# Rectifiers.net
KiCad netlist of a schematic drawn in Altium Designer
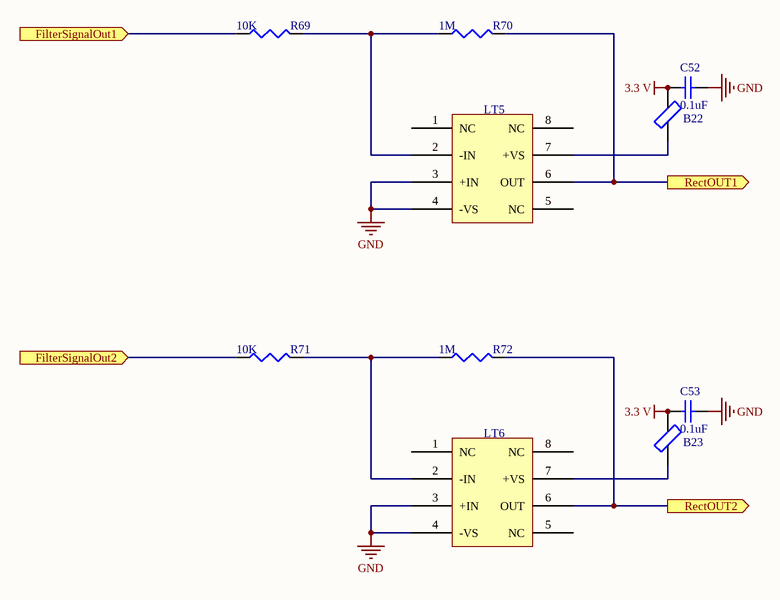
[diagram p0: Rectifiers.SchDoc]

(export (version "E")
  (design (tool "Eeschema 10.0.6"))
  (components
    (comp (ref "B22")
      (value "Ferrite Bead")
      (footprint "Resistor 0603")
      (libsource (lib "PMUD") (part "Ferrite Bead"))
    )
    (comp (ref "B23")
      (value "Ferrite Bead")
      (footprint "Resistor 0603")
      (libsource (lib "PMUD") (part "Ferrite Bead"))
    )
    (comp (ref "C52")
      (value "0.1uF")
      (footprint "C1206")
      (description "Capacitor (Semiconductor SIM Model)")
      (fields (field (name "Comment") ".1uF 20V Ceramic Low ESR") (field (name "PUBLISHER") "Altium Limited"))
      (libsource (lib "Miscellaneous Devices") (part "Cap Semi"))
    )
    (comp (ref "C53")
      (value "0.1uF")
      (footprint "C1206")
      (description "Capacitor (Semiconductor SIM Model)")
      (fields (field (name "Comment") ".1uF 20V Ceramic Low ESR") (field (name "PUBLISHER") "Altium Limited"))
      (libsource (lib "Miscellaneous Devices") (part "Cap Semi"))
    )
    (comp (ref "LT5")
      (value "LT1677 SO8 Package")
      (footprint "SO8")
      (libsource (lib "My Parts Sch Components") (part "LT1677"))
    )
    (comp (ref "LT6")
      (value "LT1677 SO8 Package")
      (footprint "SO8")
      (libsource (lib "My Parts Sch Components") (part "LT1677"))
    )
    (comp (ref "R69")
      (value "10K")
      (footprint "Capacitor 0603")
      (description "Resistor")
      (fields (field (name "Comment") "1/16 118K watt 1%") (field (name "PUBLISHER") "Altium Limited"))
      (libsource (lib "CustomParts_MattW") (part "Res3"))
    )
    (comp (ref "R70")
      (value "1M")
      (footprint "Capacitor 0603")
      (description "Resistor")
      (fields (field (name "Comment") "1/16 118K watt 1%") (field (name "PUBLISHER") "Altium Limited"))
      (libsource (lib "CustomParts_MattW") (part "Res3"))
    )
    (comp (ref "R71")
      (value "10K")
      (footprint "Capacitor 0603")
      (description "Resistor")
      (fields (field (name "Comment") "1/16 118K watt 1%") (field (name "PUBLISHER") "Altium Limited"))
      (libsource (lib "CustomParts_MattW") (part "Res3"))
    )
    (comp (ref "R72")
      (value "1M")
      (footprint "Capacitor 0603")
      (description "Resistor")
      (fields (field (name "Comment") "1/16 118K watt 1%") (field (name "PUBLISHER") "Altium Limited"))
      (libsource (lib "CustomParts_MattW") (part "Res3"))
    )
  )
  (nets
    (net (code "1") (name "/FilterSignalOut1") (class "Default")
      (node (ref "R69") (pin "1") (pinfunction "1_1") (pintype "passive"))
    )
    (net (code "2") (name "/FilterSignalOut2") (class "Default")
      (node (ref "R71") (pin "1") (pinfunction "1_1") (pintype "passive"))
    )
    (net (code "3") (name "/RectOUT1") (class "Default")
      (node (ref "LT5") (pin "6") (pinfunction "OUT_6") (pintype "passive"))
      (node (ref "R70") (pin "2") (pinfunction "2_2") (pintype "passive"))
    )
    (net (code "4") (name "/RectOUT2") (class "Default")
      (node (ref "LT6") (pin "6") (pinfunction "OUT_6") (pintype "passive"))
      (node (ref "R72") (pin "2") (pinfunction "2_2") (pintype "passive"))
    )
    (net (code "5") (name "3.3 V") (class "Default")
      (node (ref "B22") (pin "1") (pinfunction "1_1") (pintype "passive"))
      (node (ref "B23") (pin "1") (pinfunction "1_1") (pintype "passive"))
      (node (ref "C52") (pin "1") (pinfunction "1_1") (pintype "passive"))
      (node (ref "C53") (pin "1") (pinfunction "1_1") (pintype "passive"))
    )
    (net (code "6") (name "GND") (class "Default")
      (node (ref "C52") (pin "2") (pinfunction "2_2") (pintype "passive"))
      (node (ref "C53") (pin "2") (pinfunction "2_2") (pintype "passive"))
      (node (ref "LT5") (pin "3") (pinfunction "+IN_3") (pintype "passive"))
      (node (ref "LT5") (pin "4") (pinfunction "-VS_4") (pintype "passive"))
      (node (ref "LT6") (pin "3") (pinfunction "+IN_3") (pintype "passive"))
      (node (ref "LT6") (pin "4") (pinfunction "-VS_4") (pintype "passive"))
    )
    (net (code "7") (name "Net-(LT5-+VS)") (class "Default")
      (node (ref "B22") (pin "2") (pinfunction "2_2") (pintype "passive"))
      (node (ref "LT5") (pin "7") (pinfunction "+VS_7") (pintype "passive"))
    )
    (net (code "8") (name "Net-(LT5--IN)") (class "Default")
      (node (ref "LT5") (pin "2") (pinfunction "-IN_2") (pintype "passive"))
      (node (ref "R69") (pin "2") (pinfunction "2_2") (pintype "passive"))
      (node (ref "R70") (pin "1") (pinfunction "1_1") (pintype "passive"))
    )
    (net (code "9") (name "Net-(LT6-+VS)") (class "Default")
      (node (ref "B23") (pin "2") (pinfunction "2_2") (pintype "passive"))
      (node (ref "LT6") (pin "7") (pinfunction "+VS_7") (pintype "passive"))
    )
    (net (code "10") (name "Net-(LT6--IN)") (class "Default")
      (node (ref "LT6") (pin "2") (pinfunction "-IN_2") (pintype "passive"))
      (node (ref "R71") (pin "2") (pinfunction "2_2") (pintype "passive"))
      (node (ref "R72") (pin "1") (pinfunction "1_1") (pintype "passive"))
    )
    (net (code "11") (name "unconnected-(LT5-NC-Pad1)") (class "Default")
      (node (ref "LT5") (pin "1") (pinfunction "NC_1") (pintype "passive"))
    )
    (net (code "12") (name "unconnected-(LT5-NC-Pad5)") (class "Default")
      (node (ref "LT5") (pin "5") (pinfunction "NC_5") (pintype "passive"))
    )
    (net (code "13") (name "unconnected-(LT5-NC-Pad8)") (class "Default")
      (node (ref "LT5") (pin "8") (pinfunction "NC_8") (pintype "passive"))
    )
    (net (code "14") (name "unconnected-(LT6-NC-Pad1)") (class "Default")
      (node (ref "LT6") (pin "1") (pinfunction "NC_1") (pintype "passive"))
    )
    (net (code "15") (name "unconnected-(LT6-NC-Pad5)") (class "Default")
      (node (ref "LT6") (pin "5") (pinfunction "NC_5") (pintype "passive"))
    )
    (net (code "16") (name "unconnected-(LT6-NC-Pad8)") (class "Default")
      (node (ref "LT6") (pin "8") (pinfunction "NC_8") (pintype "passive"))
    )
  )
)
